# SCH_Acid_Charger_-_V1.net
KiCad netlist of a schematic drawn in EasyEDA
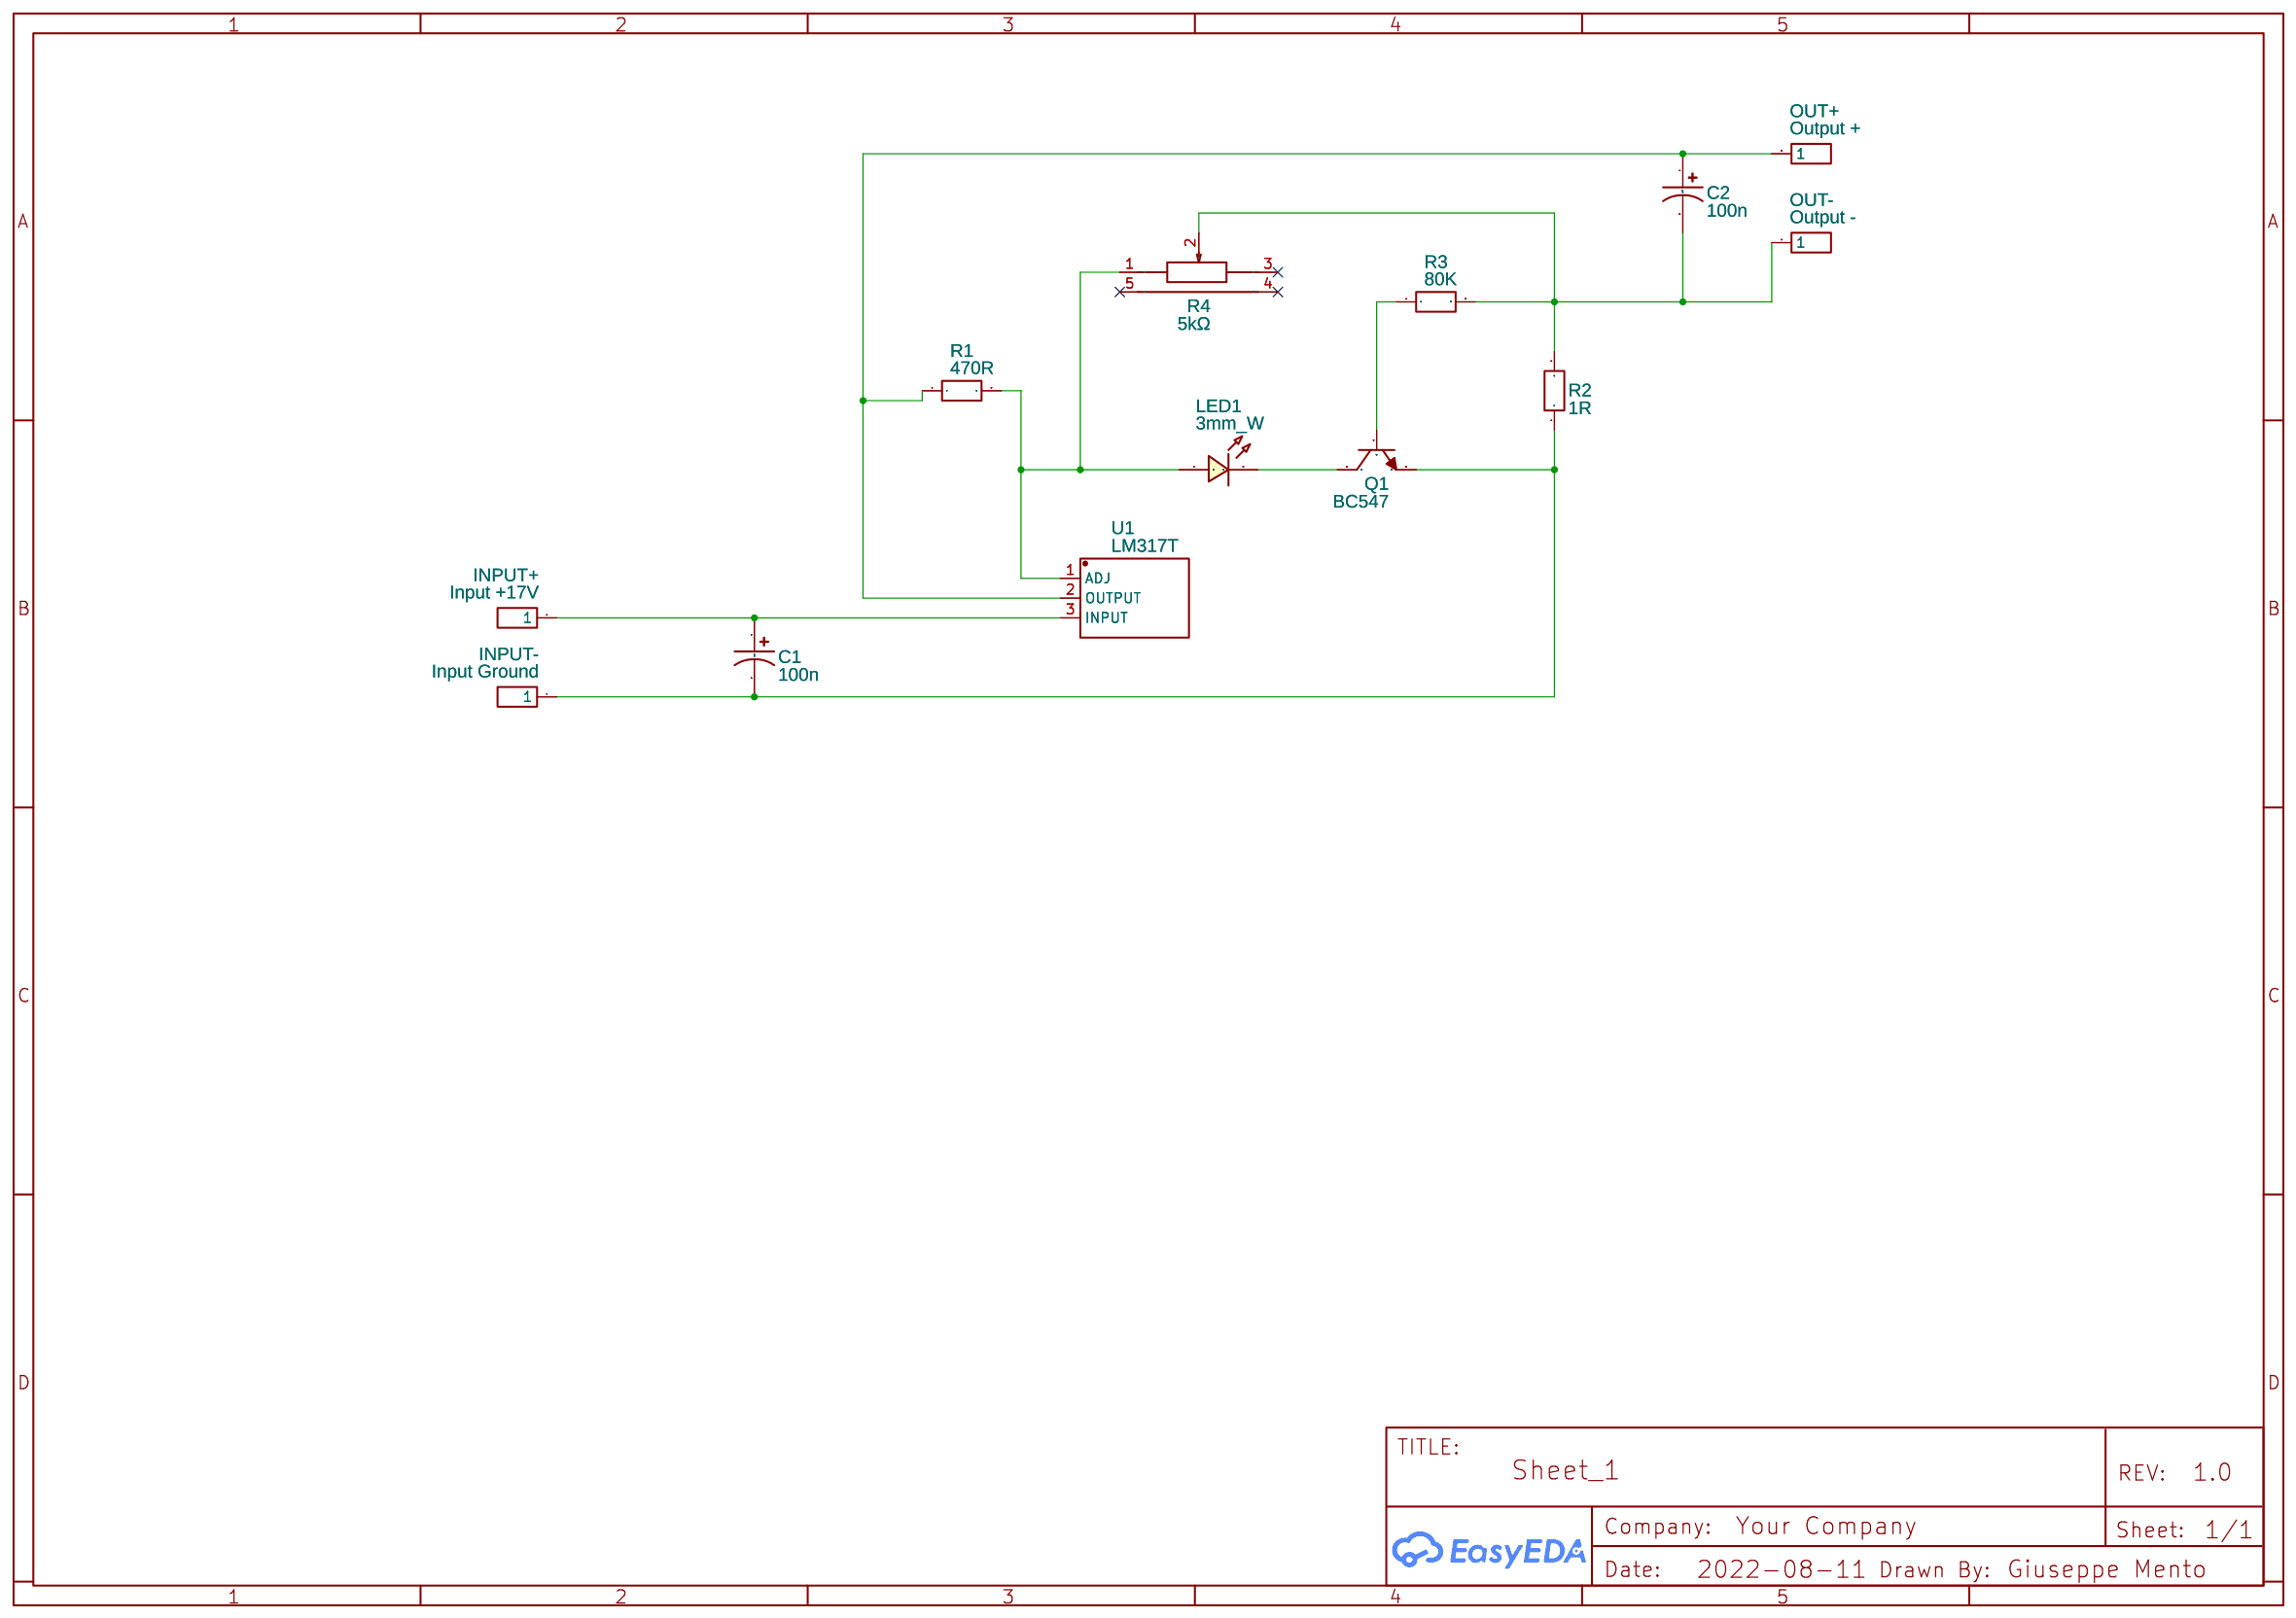
[diagram p0: schematic sheet]

(export (version "E")
  (design (tool "Eeschema 10.0.6"))
  (components
    (comp (ref "C1") (value "100n") (libsource (lib "") (part "CE_TH_D3.0×F1.5_US")))
    (comp (ref "C2") (value "100n") (libsource (lib "") (part "CE_TH_D3.0×F1.5_US")))
    (comp (ref "INPUT+")
      (value "Input +17V")
      (fields (field (name "BOM_Supplier Part") "C81276"))
      (libsource (lib "") (part "HDR-M-2.54_1x1"))
    )
    (comp (ref "INPUT-")
      (value "Input Ground")
      (fields (field (name "BOM_Supplier Part") "C81276"))
      (libsource (lib "") (part "HDR-M-2.54_1x1_1"))
    )
    (comp (ref "LED1")
      (value "3mm_W")
      (fields
        (field (name "BOM_Manufacturer Part") "204-10SUBC/S400-A4")
        (field (name "BOM_Supplier Part") "C86881")
      )
      (libsource (lib "") (part "LED-TH-3mm_B"))
    )
    (comp (ref "OUT+")
      (value "Output +")
      (fields (field (name "BOM_Supplier Part") "C81276"))
      (libsource (lib "") (part "HDR-M-2.54_1x1_2"))
    )
    (comp (ref "OUT-")
      (value "Output -")
      (fields (field (name "BOM_Supplier Part") "C81276"))
      (libsource (lib "") (part "HDR-M-2.54_1x1_3"))
    )
    (comp (ref "Q1")
      (value "BC547")
      (fields (field (name "BOM_Supplier Part") "C2910381"))
      (libsource (lib "") (part "BC547"))
    )
    (comp (ref "R1") (value "470R") (libsource (lib "") (part "R_AXIAL-0.6_EU")))
    (comp (ref "R2") (value "1R") (libsource (lib "") (part "R_AXIAL-0.6_EU_1")))
    (comp (ref "R3") (value "80K") (libsource (lib "") (part "R_AXIAL-0.6_EU")))
    (comp (ref "R4")
      (value "5kΩ")
      (fields
        (field (name "BOM_Manufacturer Part") "RK09K1130BM4")
        (field (name "BOM_Supplier Part") "C470293")
      )
      (libsource (lib "") (part "RK09K1130BM4"))
    )
    (comp (ref "U1")
      (value "LM317T")
      (fields (field (name "BOM_Supplier Part") "C361026"))
      (libsource (lib "") (part "LM317T"))
    )
  )
  (nets
    (net (code "1") (name "Net-(C2-Pad2)") (class "Default")
      (node (ref "C2") (pin "2") (pinfunction "2_2") (pintype "unspecified"))
      (node (ref "OUT-") (pin "1") (pinfunction "1_1") (pintype "input"))
      (node (ref "R2") (pin "2") (pinfunction "2_2") (pintype "unspecified"))
      (node (ref "R3") (pin "2") (pinfunction "2_2") (pintype "unspecified"))
      (node (ref "R4") (pin "2") (pinfunction "2_2") (pintype "unspecified"))
    )
    (net (code "2") (name "Net-(Q1-B)") (class "Default")
      (node (ref "Q1") (pin "2") (pinfunction "B_2") (pintype "unspecified"))
      (node (ref "R3") (pin "1") (pinfunction "1_1") (pintype "unspecified"))
    )
    (net (code "3") (name "Net-(Q1-C)") (class "Default")
      (node (ref "LED1") (pin "2") (pinfunction "2_2") (pintype "unspecified"))
      (node (ref "Q1") (pin "1") (pinfunction "C_1") (pintype "unspecified"))
    )
    (net (code "4") (name "Net-(Q1-E)") (class "Default")
      (node (ref "C1") (pin "2") (pinfunction "2_2") (pintype "unspecified"))
      (node (ref "INPUT-") (pin "1") (pinfunction "1_1") (pintype "input"))
      (node (ref "Q1") (pin "3") (pinfunction "E_3") (pintype "unspecified"))
      (node (ref "R2") (pin "1") (pinfunction "1_1") (pintype "unspecified"))
    )
    (net (code "5") (name "Net-(U1-ADJ)") (class "Default")
      (node (ref "LED1") (pin "1") (pinfunction "1_1") (pintype "unspecified"))
      (node (ref "R1") (pin "2") (pinfunction "2_2") (pintype "unspecified"))
      (node (ref "R4") (pin "1") (pinfunction "1_1") (pintype "unspecified"))
      (node (ref "U1") (pin "1") (pinfunction "ADJ_1") (pintype "unspecified"))
    )
    (net (code "6") (name "Net-(U1-INPUT)") (class "Default")
      (node (ref "C1") (pin "1") (pinfunction "1_1") (pintype "unspecified"))
      (node (ref "INPUT+") (pin "1") (pinfunction "1_1") (pintype "input"))
      (node (ref "U1") (pin "3") (pinfunction "INPUT_3") (pintype "unspecified"))
    )
    (net (code "7") (name "Net-(U1-OUTPUT)") (class "Default")
      (node (ref "C2") (pin "1") (pinfunction "1_1") (pintype "unspecified"))
      (node (ref "OUT+") (pin "1") (pinfunction "1_1") (pintype "input"))
      (node (ref "R1") (pin "1") (pinfunction "1_1") (pintype "unspecified"))
      (node (ref "U1") (pin "2") (pinfunction "OUTPUT_2") (pintype "unspecified"))
    )
    (net (code "8") (name "unconnected-(R4-EH-Pad4)") (class "Default")
      (node (ref "R4") (pin "4") (pinfunction "EH_4") (pintype "unspecified+no_connect"))
    )
    (net (code "9") (name "unconnected-(R4-EH-Pad5)") (class "Default")
      (node (ref "R4") (pin "5") (pinfunction "EH_5") (pintype "unspecified+no_connect"))
    )
    (net (code "10") (name "unconnected-(R4-Pad3)") (class "Default")
      (node (ref "R4") (pin "3") (pinfunction "3_3") (pintype "unspecified+no_connect"))
    )
  )
)
